# dsau-dds-connector.net
KiCad netlist of a schematic drawn in Altium Designer
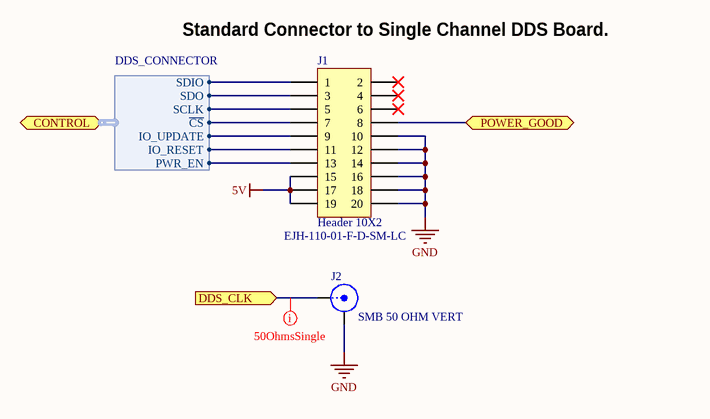
[diagram p0: dsau-dds-connector.SchDoc]

(export (version "E")
  (design (tool "Eeschema 10.0.6"))
  (components
    (comp (ref "J1")
      (value "Header 10X2")
      (footprint "HDR2X10")
      (description "Header, 10-Pin, Dual row")
      (fields
        (field (name "MANUFACTURER") "Samtec")
        (field (name "MANUFACTURER PART NUMBER") "EJH-110-01-F-D-SM-LC")
        (field (name "SUPPLIER PART NUMBER 1") "EJH-110-01-F-D-SM-LC")
        (field (name "PUBLISHER") "Altium Limited")
      )
      (libsource (lib "Miscellaneous Connectors") (part "Header 10X2"))
    )
    (comp (ref "J2")
      (value "SMB 50 OHM VERT")
      (footprint "MOLEX_SMBVERT_731000207")
      (description "SMB Straight Connector")
      (fields
        (field (name "MANUFACTURER") "Molex Inc")
        (field (name "MANUFACTURER PART NUMBER") "0731000207")
        (field (name "PUBLISHER") "Altium Limited")
      )
      (libsource (lib "Miscellaneous Connectors") (part "SMB"))
    )
  )
  (nets
    (net (code "2") (name "/DDS_CLK") (class "Default")
      (node (ref "J2") (pin "1") (pinfunction "X_1") (pintype "passive"))
    )
    (net (code "3") (name "/IO_RESET") (class "Default")
      (node (ref "J1") (pin "11") (pinfunction "11_11") (pintype "passive"))
    )
    (net (code "4") (name "/IO_UPDATE") (class "Default")
      (node (ref "J1") (pin "9") (pinfunction "9_9") (pintype "passive"))
    )
    (net (code "5") (name "/POWER_GOOD") (class "Default")
      (node (ref "J1") (pin "8") (pinfunction "8_8") (pintype "passive"))
    )
    (net (code "6") (name "/PWR_EN") (class "Default")
      (node (ref "J1") (pin "13") (pinfunction "13_13") (pintype "passive"))
    )
    (net (code "7") (name "/SCLK") (class "Default")
      (node (ref "J1") (pin "5") (pinfunction "5_5") (pintype "passive"))
    )
    (net (code "8") (name "/SDIO") (class "Default")
      (node (ref "J1") (pin "1") (pinfunction "1_1") (pintype "passive"))
    )
    (net (code "9") (name "/SDO") (class "Default")
      (node (ref "J1") (pin "3") (pinfunction "3_3") (pintype "passive"))
    )
    (net (code "11") (name "/~{CS}") (class "Default")
      (node (ref "J1") (pin "7") (pinfunction "7_7") (pintype "passive"))
    )
    (net (code "12") (name "5V") (class "Default")
      (node (ref "J1") (pin "15") (pinfunction "15_15") (pintype "passive"))
      (node (ref "J1") (pin "17") (pinfunction "17_17") (pintype "passive"))
      (node (ref "J1") (pin "19") (pinfunction "19_19") (pintype "passive"))
    )
    (net (code "13") (name "GND") (class "Default")
      (node (ref "J1") (pin "10") (pinfunction "10_10") (pintype "passive"))
      (node (ref "J1") (pin "12") (pinfunction "12_12") (pintype "passive"))
      (node (ref "J1") (pin "14") (pinfunction "14_14") (pintype "passive"))
      (node (ref "J1") (pin "16") (pinfunction "16_16") (pintype "passive"))
      (node (ref "J1") (pin "18") (pinfunction "18_18") (pintype "passive"))
      (node (ref "J1") (pin "20") (pinfunction "20_20") (pintype "passive"))
      (node (ref "J2") (pin "2") (pinfunction "Y_2") (pintype "passive"))
    )
    (net (code "14") (name "unconnected-(J1-Pad2)") (class "Default")
      (node (ref "J1") (pin "2") (pinfunction "2_2") (pintype "passive+no_connect"))
    )
    (net (code "15") (name "unconnected-(J1-Pad4)") (class "Default")
      (node (ref "J1") (pin "4") (pinfunction "4_4") (pintype "passive+no_connect"))
    )
    (net (code "16") (name "unconnected-(J1-Pad6)") (class "Default")
      (node (ref "J1") (pin "6") (pinfunction "6_6") (pintype "passive+no_connect"))
    )
  )
)
